# rtc_esp8266.net
KiCad netlist of a schematic drawn in EAGLE
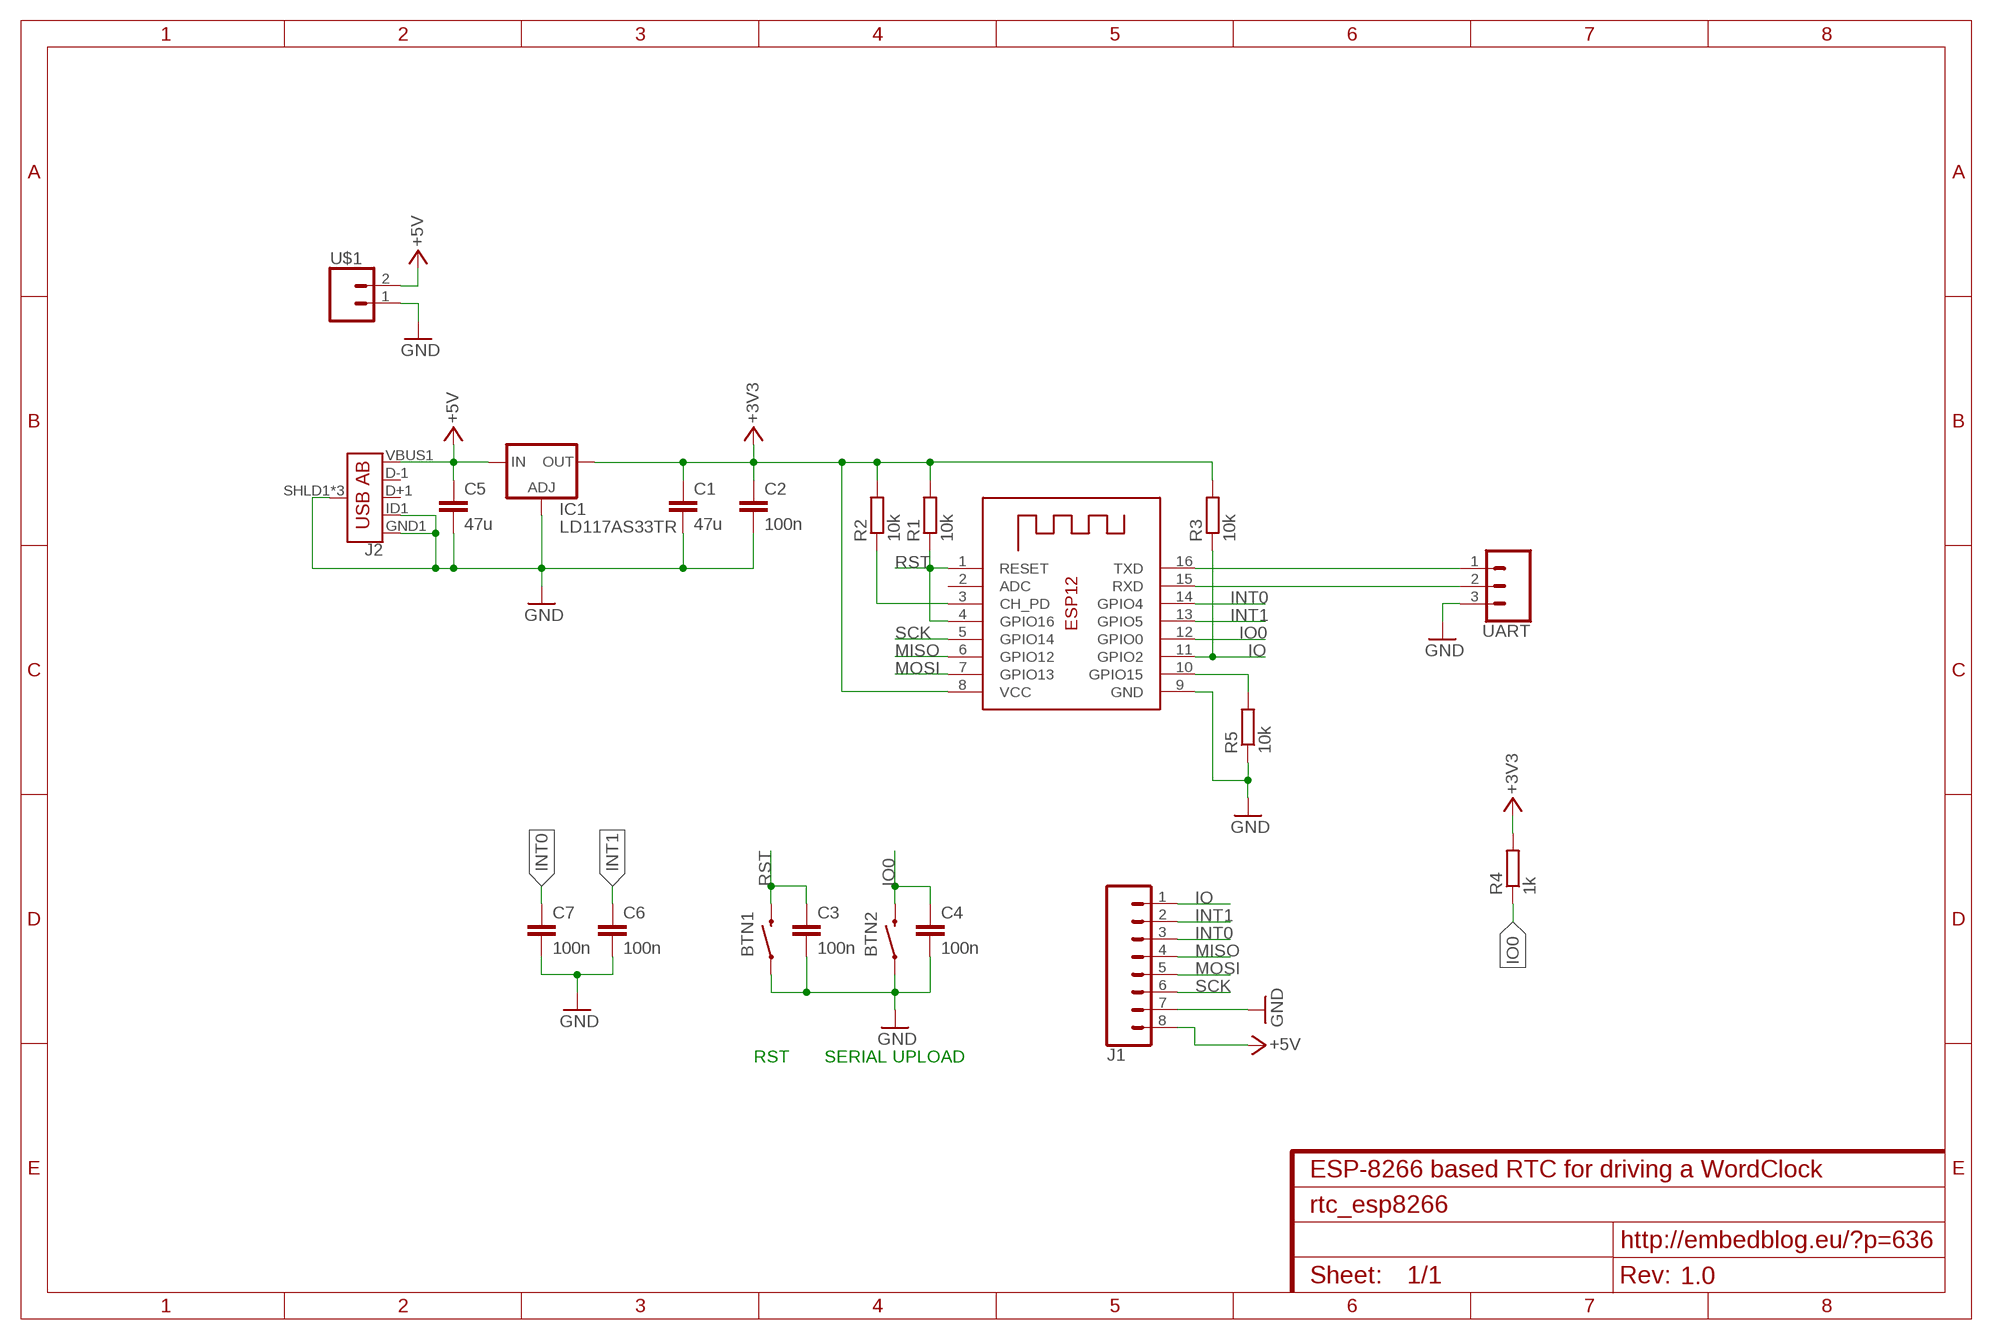
[diagram p0: schematic, sheet 1]

(export (version "E")
  (design (tool "Eeschema 10.0.6"))
  (components
    (comp (ref "BTN1")
      (value "MOMENTARY-SWITCH-SPST-SMD-5.2MM")
      (footprint "eagle-import:TACTILE_SWITCH_SMD_5.2MM")
      (libsource (lib "eagle-import") (part "MOMENTARY-SWITCH-SPST-SMD-5.2MM"))
    )
    (comp (ref "BTN2")
      (value "MOMENTARY-SWITCH-SPST-SMD-5.2MM")
      (footprint "eagle-import:TACTILE_SWITCH_SMD_5.2MM")
      (libsource (lib "eagle-import") (part "MOMENTARY-SWITCH-SPST-SMD-5.2MM"))
    )
    (comp (ref "C1")
      (value "47u")
      (footprint "eagle-import:C1206")
      (libsource (lib "eagle-import") (part "C-EUC1206"))
    )
    (comp (ref "C2")
      (value "100n")
      (footprint "eagle-import:C1206")
      (libsource (lib "eagle-import") (part "C-EUC1206"))
    )
    (comp (ref "C3")
      (value "100n")
      (footprint "eagle-import:C1206")
      (libsource (lib "eagle-import") (part "C-EUC1206"))
    )
    (comp (ref "C4")
      (value "100n")
      (footprint "eagle-import:C1206")
      (libsource (lib "eagle-import") (part "C-EUC1206"))
    )
    (comp (ref "C5")
      (value "47u")
      (footprint "eagle-import:C1206")
      (libsource (lib "eagle-import") (part "C-EUC1206"))
    )
    (comp (ref "C6")
      (value "100n")
      (footprint "eagle-import:C1206")
      (libsource (lib "eagle-import") (part "C-EUC1206"))
    )
    (comp (ref "C7")
      (value "100n")
      (footprint "eagle-import:C1206")
      (libsource (lib "eagle-import") (part "C-EUC1206"))
    )
    (comp (ref "IC1")
      (value "LD117AS33TR")
      (footprint "eagle-import:SOT223")
      (libsource (lib "eagle-import") (part "LD117A?S33TR"))
    )
    (comp (ref "J1")
      (value "CONN_08\"")
      (footprint "eagle-import:1X08")
      (libsource (lib "eagle-import") (part "CONN_08{dblquote}"))
    )
    (comp (ref "J2")
      (value "USB_AB_SMT")
      (footprint "eagle-import:USB-AB-MICRO-SMD")
      (libsource (lib "eagle-import") (part "USB_AB_SMT"))
    )
    (comp (ref "R1")
      (value "10k")
      (footprint "eagle-import:R1206")
      (libsource (lib "eagle-import") (part "R-EU_R1206"))
    )
    (comp (ref "R2")
      (value "10k")
      (footprint "eagle-import:R1206")
      (libsource (lib "eagle-import") (part "R-EU_R1206"))
    )
    (comp (ref "R3")
      (value "10k")
      (footprint "eagle-import:R1206")
      (libsource (lib "eagle-import") (part "R-EU_R1206"))
    )
    (comp (ref "R4")
      (value "1k")
      (footprint "eagle-import:R1206")
      (libsource (lib "eagle-import") (part "R-EU_R1206"))
    )
    (comp (ref "R5")
      (value "10k")
      (footprint "eagle-import:R1206")
      (libsource (lib "eagle-import") (part "R-EU_R1206"))
    )
    (comp (ref "U$1")
      (value "CONN_02PTH3")
      (footprint "eagle-import:1X02_LONGPADS")
      (libsource (lib "eagle-import") (part "CONN_02PTH3"))
    )
    (comp (ref "UART")
      (value "455-1750-1-ND")
      (footprint "eagle-import:1X03")
      (libsource (lib "eagle-import") (part "CONN_03"))
    )
    (comp (ref "X1")
      (value "ESP-12")
      (footprint "eagle-import:ESP-12")
      (libsource (lib "eagle-import") (part "ESP-12"))
    )
  )
  (nets
    (net (code "1") (name "+3V3") (class "Default")
      (node (ref "C1") (pin "1") (pinfunction "1_1") (pintype "passive"))
      (node (ref "C2") (pin "1") (pinfunction "1_1") (pintype "passive"))
      (node (ref "IC1") (pin "4") (pinfunction "OUT_4") (pintype "passive"))
      (node (ref "R1") (pin "2") (pinfunction "2_2") (pintype "passive"))
      (node (ref "R2") (pin "2") (pinfunction "2_2") (pintype "passive"))
      (node (ref "R3") (pin "2") (pinfunction "2_2") (pintype "passive"))
      (node (ref "R4") (pin "2") (pinfunction "2_2") (pintype "passive"))
      (node (ref "X1") (pin "8") (pinfunction "VCC_8") (pintype "power_in"))
    )
    (net (code "2") (name "+5V") (class "Default")
      (node (ref "C5") (pin "1") (pinfunction "1_1") (pintype "passive"))
      (node (ref "IC1") (pin "3") (pinfunction "IN_3") (pintype "input"))
      (node (ref "J1") (pin "8") (pinfunction "8_8") (pintype "passive"))
      (node (ref "J2") (pin "VBUS1") (pinfunction "VBUS_VBUS1") (pintype "power_in"))
      (node (ref "U$1") (pin "2") (pinfunction "2_2") (pintype "passive"))
    )
    (net (code "3") (name "/IO") (class "Default")
      (node (ref "J1") (pin "1") (pinfunction "1_1") (pintype "passive"))
      (node (ref "R3") (pin "1") (pinfunction "1_1") (pintype "passive"))
      (node (ref "X1") (pin "11") (pinfunction "GPIO2_11") (pintype "bidirectional"))
    )
    (net (code "4") (name "/MISO") (class "Default")
      (node (ref "J1") (pin "4") (pinfunction "4_4") (pintype "passive"))
      (node (ref "X1") (pin "6") (pinfunction "GPIO12_6") (pintype "bidirectional"))
    )
    (net (code "5") (name "/MOSI") (class "Default")
      (node (ref "J1") (pin "5") (pinfunction "5_5") (pintype "passive"))
      (node (ref "X1") (pin "7") (pinfunction "GPIO13_7") (pintype "bidirectional"))
    )
    (net (code "6") (name "/RST") (class "Default")
      (node (ref "BTN1") (pin "3") (pinfunction "2_3") (pintype "passive"))
      (node (ref "C3") (pin "1") (pinfunction "1_1") (pintype "passive"))
      (node (ref "R1") (pin "1") (pinfunction "1_1") (pintype "passive"))
      (node (ref "X1") (pin "1") (pinfunction "RESET_1") (pintype "input"))
      (node (ref "X1") (pin "4") (pinfunction "GPIO16_4") (pintype "bidirectional"))
    )
    (net (code "7") (name "/SCK") (class "Default")
      (node (ref "J1") (pin "6") (pinfunction "6_6") (pintype "passive"))
      (node (ref "X1") (pin "5") (pinfunction "GPIO14_5") (pintype "bidirectional"))
    )
    (net (code "8") (name "GND") (class "Default")
      (node (ref "BTN1") (pin "1") (pinfunction "1_1") (pintype "passive"))
      (node (ref "BTN2") (pin "1") (pinfunction "1_1") (pintype "passive"))
      (node (ref "C1") (pin "2") (pinfunction "2_2") (pintype "passive"))
      (node (ref "C2") (pin "2") (pinfunction "2_2") (pintype "passive"))
      (node (ref "C3") (pin "2") (pinfunction "2_2") (pintype "passive"))
      (node (ref "C4") (pin "2") (pinfunction "2_2") (pintype "passive"))
      (node (ref "C5") (pin "2") (pinfunction "2_2") (pintype "passive"))
      (node (ref "C6") (pin "2") (pinfunction "2_2") (pintype "passive"))
      (node (ref "C7") (pin "2") (pinfunction "2_2") (pintype "passive"))
      (node (ref "IC1") (pin "1") (pinfunction "ADJ_1") (pintype "input"))
      (node (ref "J1") (pin "7") (pinfunction "7_7") (pintype "passive"))
      (node (ref "J2") (pin "GND1") (pinfunction "GND_GND1") (pintype "power_in"))
      (node (ref "J2") (pin "ID1") (pinfunction "USBID_ID1") (pintype "bidirectional"))
      (node (ref "J2") (pin "SHLD1") (pinfunction "SHIELD_SHLD1") (pintype "bidirectional"))
      (node (ref "J2") (pin "SHLD2") (pinfunction "SHIELD_SHLD2") (pintype "bidirectional"))
      (node (ref "J2") (pin "SHLD3") (pinfunction "SHIELD_SHLD3") (pintype "bidirectional"))
      (node (ref "R5") (pin "1") (pinfunction "1_1") (pintype "passive"))
      (node (ref "U$1") (pin "1") (pinfunction "1_1") (pintype "passive"))
      (node (ref "UART") (pin "3") (pinfunction "3_3") (pintype "passive"))
      (node (ref "X1") (pin "9") (pinfunction "GND_9") (pintype "power_in"))
    )
    (net (code "9") (name "INT0") (class "Default")
      (node (ref "C7") (pin "1") (pinfunction "1_1") (pintype "passive"))
      (node (ref "J1") (pin "3") (pinfunction "3_3") (pintype "passive"))
      (node (ref "X1") (pin "14") (pinfunction "GPIO4_14") (pintype "bidirectional"))
    )
    (net (code "10") (name "INT1") (class "Default")
      (node (ref "C6") (pin "1") (pinfunction "1_1") (pintype "passive"))
      (node (ref "J1") (pin "2") (pinfunction "2_2") (pintype "passive"))
      (node (ref "X1") (pin "13") (pinfunction "GPIO5_13") (pintype "bidirectional"))
    )
    (net (code "11") (name "IO0") (class "Default")
      (node (ref "BTN2") (pin "3") (pinfunction "2_3") (pintype "passive"))
      (node (ref "C4") (pin "1") (pinfunction "1_1") (pintype "passive"))
      (node (ref "R4") (pin "1") (pinfunction "1_1") (pintype "passive"))
      (node (ref "X1") (pin "12") (pinfunction "GPIO0_12") (pintype "bidirectional"))
    )
    (net (code "12") (name "Net-(X1-CH_PD)") (class "Default")
      (node (ref "R2") (pin "1") (pinfunction "1_1") (pintype "passive"))
      (node (ref "X1") (pin "3") (pinfunction "CH_PD_3") (pintype "input"))
    )
    (net (code "13") (name "Net-(X1-GPIO15)") (class "Default")
      (node (ref "R5") (pin "2") (pinfunction "2_2") (pintype "passive"))
      (node (ref "X1") (pin "10") (pinfunction "GPIO15_10") (pintype "bidirectional"))
    )
    (net (code "14") (name "Net-(X1-RXD)") (class "Default")
      (node (ref "UART") (pin "2") (pinfunction "2_2") (pintype "passive"))
      (node (ref "X1") (pin "15") (pinfunction "RXD_15") (pintype "input"))
    )
    (net (code "15") (name "Net-(X1-TXD)") (class "Default")
      (node (ref "UART") (pin "1") (pinfunction "1_1") (pintype "passive"))
      (node (ref "X1") (pin "16") (pinfunction "TXD_16") (pintype "output"))
    )
    (net (code "16") (name "unconnected-(J2-D+-PadD+1)") (class "Default")
      (node (ref "J2") (pin "D+1") (pinfunction "D+_D+1") (pintype "bidirectional"))
    )
    (net (code "17") (name "unconnected-(J2-D--PadD-1)") (class "Default")
      (node (ref "J2") (pin "D-1") (pinfunction "D-_D-1") (pintype "bidirectional"))
    )
    (net (code "18") (name "unconnected-(X1-ADC-Pad2)") (class "Default")
      (node (ref "X1") (pin "2") (pinfunction "ADC_2") (pintype "passive"))
    )
  )
)
